# STPM01_230VAC_Rogowski.net
KiCad netlist of a schematic drawn in EAGLE
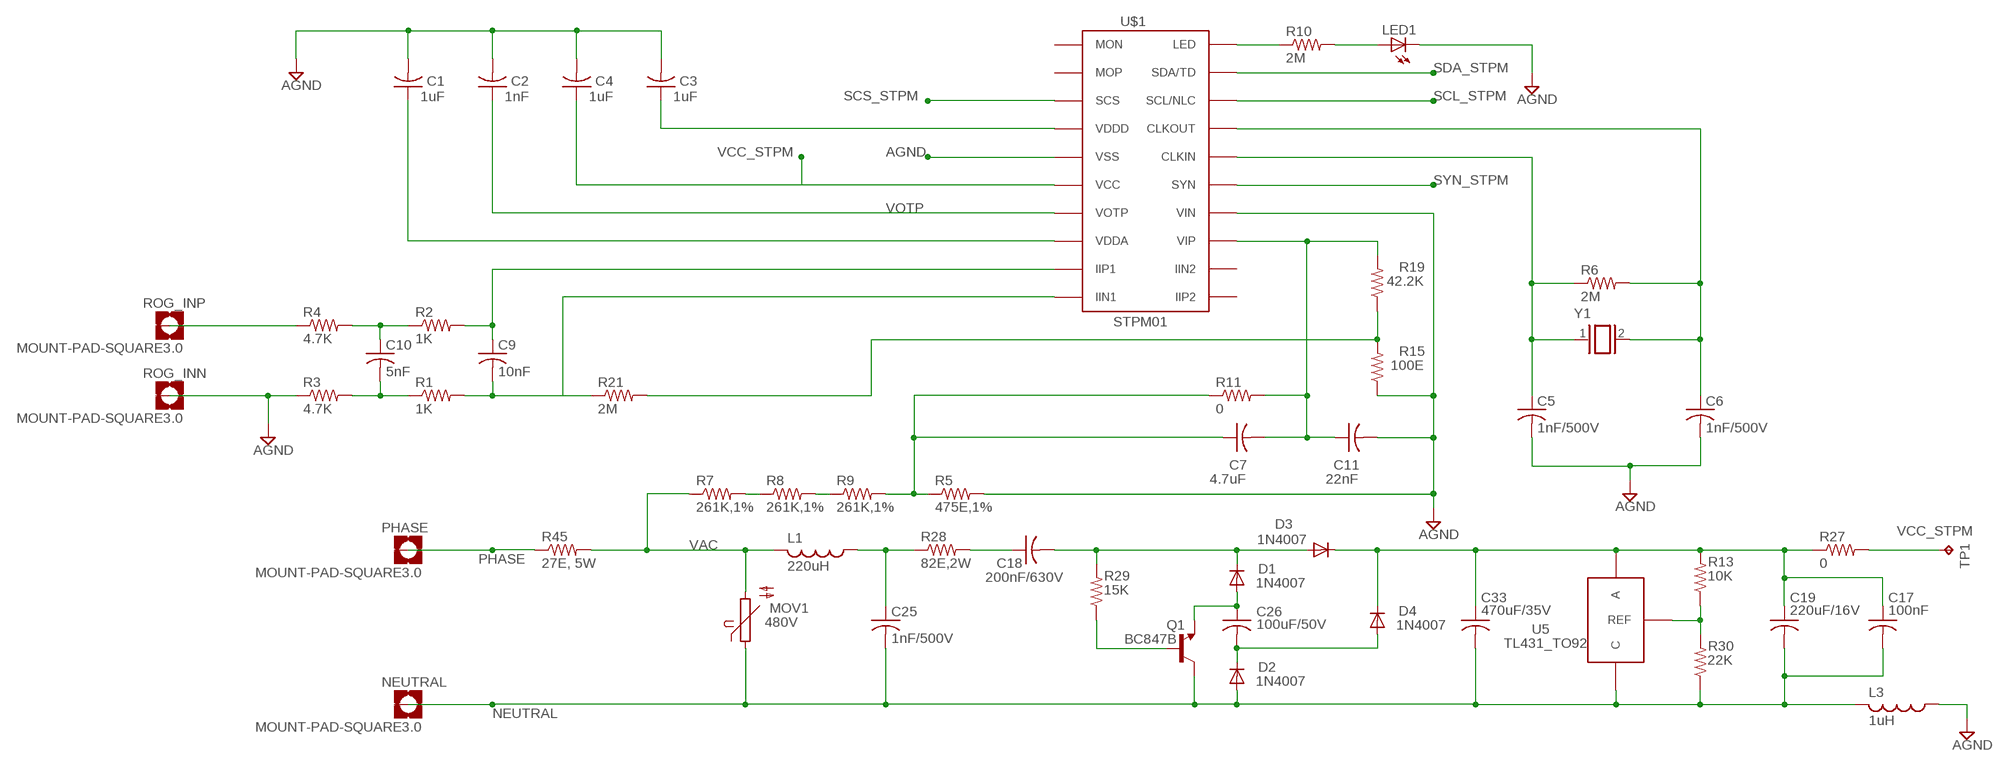
[diagram p0: schematic, sheet 1]

(export (version "E")
  (design (tool "Eeschema 10.0.6"))
  (components
    (comp (ref "C1")
      (value "1uF")
      (footprint "eagle-import:C025-060X050")
      (libsource (lib "eagle-import") (part "resistor_C-US025-060X050"))
    )
    (comp (ref "C2")
      (value "1nF")
      (footprint "eagle-import:C025-060X050")
      (libsource (lib "eagle-import") (part "resistor_C-US025-060X050"))
    )
    (comp (ref "C3")
      (value "1uF")
      (footprint "eagle-import:C025-060X050")
      (libsource (lib "eagle-import") (part "resistor_C-US025-060X050"))
    )
    (comp (ref "C4")
      (value "1uF")
      (footprint "eagle-import:C025-060X050")
      (libsource (lib "eagle-import") (part "resistor_C-US025-060X050"))
    )
    (comp (ref "C5")
      (value "1nF/500V")
      (footprint "eagle-import:C025-060X050")
      (libsource (lib "eagle-import") (part "resistor_C-US025-060X050"))
    )
    (comp (ref "C6")
      (value "1nF/500V")
      (footprint "eagle-import:C025-060X050")
      (libsource (lib "eagle-import") (part "resistor_C-US025-060X050"))
    )
    (comp (ref "C7")
      (value "4.7uF")
      (footprint "eagle-import:C050-024X044")
      (libsource (lib "eagle-import") (part "resistor_C-US050-024X044"))
    )
    (comp (ref "C9")
      (value "10nF")
      (footprint "eagle-import:C025-060X050")
      (libsource (lib "eagle-import") (part "resistor_C-US025-060X050"))
    )
    (comp (ref "C10")
      (value "5nF")
      (footprint "eagle-import:C025-060X050")
      (libsource (lib "eagle-import") (part "resistor_C-US025-060X050"))
    )
    (comp (ref "C11")
      (value "22nF")
      (footprint "eagle-import:C050-024X044")
      (libsource (lib "eagle-import") (part "resistor_C-US050-024X044"))
    )
    (comp (ref "C17")
      (value "100nF")
      (footprint "eagle-import:C025-060X050")
      (libsource (lib "eagle-import") (part "resistor_C-US025-060X050"))
    )
    (comp (ref "C18")
      (value "200nF/630V")
      (footprint "eagle-import:C050-024X044")
      (libsource (lib "eagle-import") (part "resistor_C-US050-024X044"))
    )
    (comp (ref "C19")
      (value "220uF/16V")
      (footprint "eagle-import:C025-060X050")
      (libsource (lib "eagle-import") (part "resistor_C-US025-060X050"))
    )
    (comp (ref "C25")
      (value "1nF/500V")
      (footprint "eagle-import:C025-060X050")
      (libsource (lib "eagle-import") (part "resistor_C-US025-060X050"))
    )
    (comp (ref "C26")
      (value "100uF/50V")
      (footprint "eagle-import:C050-030X075")
      (libsource (lib "eagle-import") (part "C-US050-030X075"))
    )
    (comp (ref "C33")
      (value "470uF/35V")
      (footprint "eagle-import:C025-060X050")
      (libsource (lib "eagle-import") (part "resistor_C-US025-060X050"))
    )
    (comp (ref "D1")
      (value "1N4007")
      (footprint "eagle-import:DO41-10")
      (libsource (lib "eagle-import") (part "1N4004"))
    )
    (comp (ref "D2")
      (value "1N4007")
      (footprint "eagle-import:DO41-10")
      (libsource (lib "eagle-import") (part "1N4004"))
    )
    (comp (ref "D3")
      (value "1N4007")
      (footprint "eagle-import:DO41-10")
      (libsource (lib "eagle-import") (part "1N4004"))
    )
    (comp (ref "D4")
      (value "1N4007")
      (footprint "eagle-import:DO41-10")
      (libsource (lib "eagle-import") (part "1N4004"))
    )
    (comp (ref "L1")
      (value "220uH")
      (footprint "eagle-import:0204_5")
      (libsource (lib "eagle-import") (part "L-US0204/5"))
    )
    (comp (ref "L3")
      (value "1uH")
      (footprint "eagle-import:0204_5")
      (libsource (lib "eagle-import") (part "L-US0204/5"))
    )
    (comp (ref "LED1")
      (value "LEDSMT1206")
      (footprint "eagle-import:1206")
      (libsource (lib "eagle-import") (part "LEDSMT1206"))
    )
    (comp (ref "MOV1")
      (value "480V")
      (footprint "eagle-import:S14K550")
      (libsource (lib "eagle-import") (part "S14K550"))
    )
    (comp (ref "NEUTRAL")
      (value "MOUNT-PAD-SQUARE3.0")
      (footprint "eagle-import:3,0-PAD-SQUARE")
      (libsource (lib "eagle-import") (part "MOUNT-PAD-SQUARE3.0"))
    )
    (comp (ref "PHASE")
      (value "MOUNT-PAD-SQUARE3.0")
      (footprint "eagle-import:3,0-PAD-SQUARE")
      (libsource (lib "eagle-import") (part "MOUNT-PAD-SQUARE3.0"))
    )
    (comp (ref "Q1")
      (value "BC847B")
      (footprint "eagle-import:SOT23")
      (libsource (lib "eagle-import") (part "BC847"))
    )
    (comp (ref "R1")
      (value "1K")
      (footprint "eagle-import:0922V")
      (libsource (lib "eagle-import") (part "R-US_0922V"))
    )
    (comp (ref "R2")
      (value "1K")
      (footprint "eagle-import:0922V")
      (libsource (lib "eagle-import") (part "R-US_0922V"))
    )
    (comp (ref "R3")
      (value "4.7K")
      (footprint "eagle-import:0922V")
      (libsource (lib "eagle-import") (part "R-US_0922V"))
    )
    (comp (ref "R4")
      (value "4.7K")
      (footprint "eagle-import:0922V")
      (libsource (lib "eagle-import") (part "R-US_0922V"))
    )
    (comp (ref "R5")
      (value "475E,1%")
      (footprint "eagle-import:0922V")
      (libsource (lib "eagle-import") (part "R-US_0922V"))
    )
    (comp (ref "R6")
      (value "2M")
      (footprint "eagle-import:0922V")
      (libsource (lib "eagle-import") (part "R-US_0922V"))
    )
    (comp (ref "R7")
      (value "261K,1%")
      (footprint "eagle-import:0922V")
      (libsource (lib "eagle-import") (part "R-US_0922V"))
    )
    (comp (ref "R8")
      (value "261K,1%")
      (footprint "eagle-import:0922V")
      (libsource (lib "eagle-import") (part "R-US_0922V"))
    )
    (comp (ref "R9")
      (value "261K,1%")
      (footprint "eagle-import:0922V")
      (libsource (lib "eagle-import") (part "R-US_0922V"))
    )
    (comp (ref "R10")
      (value "2M")
      (footprint "eagle-import:0922V")
      (libsource (lib "eagle-import") (part "R-US_0922V"))
    )
    (comp (ref "R11")
      (value "0")
      (footprint "eagle-import:0922V")
      (libsource (lib "eagle-import") (part "R-US_0922V"))
    )
    (comp (ref "R13")
      (value "10K")
      (footprint "eagle-import:0204_5")
      (libsource (lib "eagle-import") (part "R-US_0204/5"))
    )
    (comp (ref "R15")
      (value "100E")
      (footprint "eagle-import:0204_5")
      (libsource (lib "eagle-import") (part "R-US_0204/5"))
    )
    (comp (ref "R19")
      (value "42.2K")
      (footprint "eagle-import:0204_5")
      (libsource (lib "eagle-import") (part "R-US_0204/5"))
    )
    (comp (ref "R21")
      (value "2M")
      (footprint "eagle-import:0922V")
      (libsource (lib "eagle-import") (part "R-US_0922V"))
    )
    (comp (ref "R27")
      (value "0")
      (footprint "eagle-import:0204_5")
      (libsource (lib "eagle-import") (part "R-US_0204/5"))
    )
    (comp (ref "R28")
      (value "82E,2W")
      (footprint "eagle-import:0204_5")
      (libsource (lib "eagle-import") (part "R-US_0204/5"))
    )
    (comp (ref "R29")
      (value "15K")
      (footprint "eagle-import:0204_5")
      (libsource (lib "eagle-import") (part "R-US_0204/5"))
    )
    (comp (ref "R30")
      (value "22K")
      (footprint "eagle-import:0204_5")
      (libsource (lib "eagle-import") (part "R-US_0204/5"))
    )
    (comp (ref "R45")
      (value "27E, 5W")
      (footprint "eagle-import:0922V")
      (libsource (lib "eagle-import") (part "R-US_0922V"))
    )
    (comp (ref "ROG_INN")
      (value "MOUNT-PAD-SQUARE3.0")
      (footprint "eagle-import:3,0-PAD-SQUARE")
      (libsource (lib "eagle-import") (part "MOUNT-PAD-SQUARE3.0"))
    )
    (comp (ref "ROG_INP")
      (value "MOUNT-PAD-SQUARE3.0")
      (footprint "eagle-import:3,0-PAD-SQUARE")
      (libsource (lib "eagle-import") (part "MOUNT-PAD-SQUARE3.0"))
    )
    (comp (ref "TP1")
      (value "TPB2,54")
      (footprint "eagle-import:B2,54")
      (libsource (lib "eagle-import") (part "TPB2,54"))
    )
    (comp (ref "U$1")
      (value "STPM01")
      (footprint "eagle-import:TSSOP20")
      (libsource (lib "eagle-import") (part "STPM01"))
    )
    (comp (ref "U5")
      (value "TL431_TO92")
      (footprint "eagle-import:TO92-")
      (libsource (lib "eagle-import") (part "TL431AIZ"))
    )
    (comp (ref "Y1")
      (value "XTAL/S")
      (footprint "eagle-import:QS")
      (libsource (lib "eagle-import") (part "XTAL/S"))
    )
  )
  (nets
    (net (code "1") (name "/NEUTRAL") (class "Default")
      (node (ref "C17") (pin "2") (pinfunction "2_2") (pintype "passive"))
      (node (ref "C19") (pin "2") (pinfunction "2_2") (pintype "passive"))
      (node (ref "C25") (pin "2") (pinfunction "2_2") (pintype "passive"))
      (node (ref "C33") (pin "2") (pinfunction "2_2") (pintype "passive"))
      (node (ref "D2") (pin "A") (pinfunction "A_A") (pintype "passive"))
      (node (ref "L3") (pin "2") (pinfunction "2_2") (pintype "passive"))
      (node (ref "MOV1") (pin "1") (pinfunction "1_1") (pintype "passive"))
      (node (ref "Q1") (pin "3") (pinfunction "C_3") (pintype "passive"))
      (node (ref "R30") (pin "1") (pinfunction "1_1") (pintype "passive"))
      (node (ref "U5") (pin "1") (pinfunction "C_1") (pintype "bidirectional"))
    )
    (net (code "2") (name "/PHASE") (class "Default")
      (node (ref "R45") (pin "1") (pinfunction "1_1") (pintype "passive"))
    )
    (net (code "3") (name "/SCL_STPM") (class "Default")
      (node (ref "U$1") (pin "P$18") (pinfunction "SCL/NLC_P$18") (pintype "bidirectional"))
    )
    (net (code "4") (name "/SCS_STPM") (class "Default")
      (node (ref "U$1") (pin "P$3") (pinfunction "SCS_P$3") (pintype "bidirectional"))
    )
    (net (code "5") (name "/SDA_STPM") (class "Default")
      (node (ref "U$1") (pin "P$19") (pinfunction "SDA/TD_P$19") (pintype "bidirectional"))
    )
    (net (code "6") (name "/SYN_STPM") (class "Default")
      (node (ref "U$1") (pin "P$15") (pinfunction "SYN_P$15") (pintype "bidirectional"))
    )
    (net (code "7") (name "/VAC") (class "Default")
      (node (ref "L1") (pin "2") (pinfunction "2_2") (pintype "passive"))
      (node (ref "MOV1") (pin "2") (pinfunction "2_2") (pintype "passive"))
      (node (ref "R45") (pin "2") (pinfunction "2_2") (pintype "passive"))
      (node (ref "R7") (pin "1") (pinfunction "1_1") (pintype "passive"))
    )
    (net (code "8") (name "/VCC_STPM") (class "Default")
      (node (ref "C4") (pin "1") (pinfunction "1_1") (pintype "passive"))
      (node (ref "R27") (pin "2") (pinfunction "2_2") (pintype "passive"))
      (node (ref "TP1") (pin "TP") (pinfunction "TP_TP") (pintype "input"))
      (node (ref "U$1") (pin "P$6") (pinfunction "VCC_P$6") (pintype "power_in"))
    )
    (net (code "9") (name "/VOTP") (class "Default")
      (node (ref "C2") (pin "1") (pinfunction "1_1") (pintype "passive"))
      (node (ref "U$1") (pin "P$7") (pinfunction "VOTP_P$7") (pintype "power_in"))
    )
    (net (code "10") (name "AGND") (class "Default")
      (node (ref "C1") (pin "2") (pinfunction "2_2") (pintype "passive"))
      (node (ref "C11") (pin "2") (pinfunction "2_2") (pintype "passive"))
      (node (ref "C2") (pin "2") (pinfunction "2_2") (pintype "passive"))
      (node (ref "C3") (pin "2") (pinfunction "2_2") (pintype "passive"))
      (node (ref "C4") (pin "2") (pinfunction "2_2") (pintype "passive"))
      (node (ref "C5") (pin "2") (pinfunction "2_2") (pintype "passive"))
      (node (ref "C6") (pin "2") (pinfunction "2_2") (pintype "passive"))
      (node (ref "L3") (pin "1") (pinfunction "1_1") (pintype "passive"))
      (node (ref "LED1") (pin "C") (pinfunction "C_C") (pintype "passive"))
      (node (ref "R15") (pin "1") (pinfunction "1_1") (pintype "passive"))
      (node (ref "R3") (pin "1") (pinfunction "1_1") (pintype "passive"))
      (node (ref "R5") (pin "2") (pinfunction "2_2") (pintype "passive"))
      (node (ref "U$1") (pin "P$14") (pinfunction "VIN_P$14") (pintype "input"))
      (node (ref "U$1") (pin "P$5") (pinfunction "VSS_P$5") (pintype "power_in"))
    )
    (net (code "11") (name "Net-(C7-Pad1)") (class "Default")
      (node (ref "C7") (pin "1") (pinfunction "1_1") (pintype "passive"))
      (node (ref "R11") (pin "1") (pinfunction "1_1") (pintype "passive"))
      (node (ref "R5") (pin "1") (pinfunction "1_1") (pintype "passive"))
      (node (ref "R9") (pin "2") (pinfunction "2_2") (pintype "passive"))
    )
    (net (code "12") (name "Net-(C10-Pad1)") (class "Default")
      (node (ref "C10") (pin "1") (pinfunction "1_1") (pintype "passive"))
      (node (ref "R2") (pin "1") (pinfunction "1_1") (pintype "passive"))
      (node (ref "R4") (pin "2") (pinfunction "2_2") (pintype "passive"))
    )
    (net (code "13") (name "Net-(C10-Pad2)") (class "Default")
      (node (ref "C10") (pin "2") (pinfunction "2_2") (pintype "passive"))
      (node (ref "R1") (pin "1") (pinfunction "1_1") (pintype "passive"))
      (node (ref "R3") (pin "2") (pinfunction "2_2") (pintype "passive"))
    )
    (net (code "14") (name "Net-(C18-Pad1)") (class "Default")
      (node (ref "C18") (pin "1") (pinfunction "1_1") (pintype "passive"))
      (node (ref "R28") (pin "2") (pinfunction "2_2") (pintype "passive"))
    )
    (net (code "15") (name "Net-(C18-Pad2)") (class "Default")
      (node (ref "C18") (pin "2") (pinfunction "2_2") (pintype "passive"))
      (node (ref "D1") (pin "C") (pinfunction "C_C") (pintype "passive"))
      (node (ref "D3") (pin "A") (pinfunction "A_A") (pintype "passive"))
      (node (ref "R29") (pin "2") (pinfunction "2_2") (pintype "passive"))
    )
    (net (code "16") (name "Net-(C25-Pad1)") (class "Default")
      (node (ref "C25") (pin "1") (pinfunction "1_1") (pintype "passive"))
      (node (ref "L1") (pin "1") (pinfunction "1_1") (pintype "passive"))
      (node (ref "R28") (pin "1") (pinfunction "1_1") (pintype "passive"))
    )
    (net (code "17") (name "Net-(C26-Pad2)") (class "Default")
      (node (ref "C26") (pin "2") (pinfunction "2_2") (pintype "passive"))
      (node (ref "D2") (pin "C") (pinfunction "C_C") (pintype "passive"))
      (node (ref "D4") (pin "A") (pinfunction "A_A") (pintype "passive"))
    )
    (net (code "18") (name "Net-(LED1-PadA)") (class "Default")
      (node (ref "LED1") (pin "A") (pinfunction "A_A") (pintype "passive"))
      (node (ref "R10") (pin "2") (pinfunction "2_2") (pintype "passive"))
    )
    (net (code "19") (name "Net-(Q1-B)") (class "Default")
      (node (ref "Q1") (pin "1") (pinfunction "B_1") (pintype "passive"))
      (node (ref "R29") (pin "1") (pinfunction "1_1") (pintype "passive"))
    )
    (net (code "20") (name "Net-(Q1-E)") (class "Default")
      (node (ref "C26") (pin "1") (pinfunction "1_1") (pintype "passive"))
      (node (ref "D1") (pin "A") (pinfunction "A_A") (pintype "passive"))
      (node (ref "Q1") (pin "2") (pinfunction "E_2") (pintype "passive"))
    )
    (net (code "21") (name "Net-(R7-Pad2)") (class "Default")
      (node (ref "R7") (pin "2") (pinfunction "2_2") (pintype "passive"))
      (node (ref "R8") (pin "1") (pinfunction "1_1") (pintype "passive"))
    )
    (net (code "22") (name "Net-(R8-Pad2)") (class "Default")
      (node (ref "R8") (pin "2") (pinfunction "2_2") (pintype "passive"))
      (node (ref "R9") (pin "1") (pinfunction "1_1") (pintype "passive"))
    )
    (net (code "23") (name "Net-(R15-Pad2)") (class "Default")
      (node (ref "R15") (pin "2") (pinfunction "2_2") (pintype "passive"))
      (node (ref "R19") (pin "1") (pinfunction "1_1") (pintype "passive"))
      (node (ref "R21") (pin "2") (pinfunction "2_2") (pintype "passive"))
    )
    (net (code "24") (name "Net-(U$1-CLKIN)") (class "Default")
      (node (ref "C5") (pin "1") (pinfunction "1_1") (pintype "passive"))
      (node (ref "R6") (pin "1") (pinfunction "1_1") (pintype "passive"))
      (node (ref "U$1") (pin "P$16") (pinfunction "CLKIN_P$16") (pintype "bidirectional"))
      (node (ref "Y1") (pin "1") (pinfunction "1_1") (pintype "passive"))
    )
    (net (code "25") (name "Net-(U$1-CLKOUT)") (class "Default")
      (node (ref "C6") (pin "1") (pinfunction "1_1") (pintype "passive"))
      (node (ref "R6") (pin "2") (pinfunction "2_2") (pintype "passive"))
      (node (ref "U$1") (pin "P$17") (pinfunction "CLKOUT_P$17") (pintype "bidirectional"))
      (node (ref "Y1") (pin "2") (pinfunction "2_2") (pintype "passive"))
    )
    (net (code "26") (name "Net-(U$1-IIN1)") (class "Default")
      (node (ref "C9") (pin "2") (pinfunction "2_2") (pintype "passive"))
      (node (ref "R1") (pin "2") (pinfunction "2_2") (pintype "passive"))
      (node (ref "R21") (pin "1") (pinfunction "1_1") (pintype "passive"))
      (node (ref "U$1") (pin "P$10") (pinfunction "IIN1_P$10") (pintype "input"))
    )
    (net (code "27") (name "Net-(U$1-IIP1)") (class "Default")
      (node (ref "C9") (pin "1") (pinfunction "1_1") (pintype "passive"))
      (node (ref "R2") (pin "2") (pinfunction "2_2") (pintype "passive"))
      (node (ref "U$1") (pin "P$9") (pinfunction "IIP1_P$9") (pintype "input"))
    )
    (net (code "28") (name "Net-(U$1-LED)") (class "Default")
      (node (ref "R10") (pin "1") (pinfunction "1_1") (pintype "passive"))
      (node (ref "U$1") (pin "P$20") (pinfunction "LED_P$20") (pintype "output"))
    )
    (net (code "29") (name "Net-(U$1-VDDA)") (class "Default")
      (node (ref "C1") (pin "1") (pinfunction "1_1") (pintype "passive"))
      (node (ref "U$1") (pin "P$8") (pinfunction "VDDA_P$8") (pintype "output"))
    )
    (net (code "30") (name "Net-(U$1-VDDD)") (class "Default")
      (node (ref "C3") (pin "1") (pinfunction "1_1") (pintype "passive"))
      (node (ref "U$1") (pin "P$4") (pinfunction "VDDD_P$4") (pintype "output"))
    )
    (net (code "31") (name "Net-(U$1-VIP)") (class "Default")
      (node (ref "C11") (pin "1") (pinfunction "1_1") (pintype "passive"))
      (node (ref "C7") (pin "2") (pinfunction "2_2") (pintype "passive"))
      (node (ref "R11") (pin "2") (pinfunction "2_2") (pintype "passive"))
      (node (ref "R19") (pin "2") (pinfunction "2_2") (pintype "passive"))
      (node (ref "U$1") (pin "P$13") (pinfunction "VIP_P$13") (pintype "input"))
    )
    (net (code "32") (name "Net-(U5-A)") (class "Default")
      (node (ref "C17") (pin "1") (pinfunction "1_1") (pintype "passive"))
      (node (ref "C19") (pin "1") (pinfunction "1_1") (pintype "passive"))
      (node (ref "C33") (pin "1") (pinfunction "1_1") (pintype "passive"))
      (node (ref "D3") (pin "C") (pinfunction "C_C") (pintype "passive"))
      (node (ref "D4") (pin "C") (pinfunction "C_C") (pintype "passive"))
      (node (ref "R13") (pin "2") (pinfunction "2_2") (pintype "passive"))
      (node (ref "R27") (pin "1") (pinfunction "1_1") (pintype "passive"))
      (node (ref "U5") (pin "2") (pinfunction "A_2") (pintype "bidirectional"))
    )
    (net (code "33") (name "Net-(U5-REF)") (class "Default")
      (node (ref "R13") (pin "1") (pinfunction "1_1") (pintype "passive"))
      (node (ref "R30") (pin "2") (pinfunction "2_2") (pintype "passive"))
      (node (ref "U5") (pin "3") (pinfunction "REF_3") (pintype "input"))
    )
    (net (code "34") (name "unconnected-(NEUTRAL-MOUNT-PadB3,0)") (class "Default")
      (node (ref "NEUTRAL") (pin "B3,0") (pinfunction "MOUNT_B3,0") (pintype "passive"))
    )
    (net (code "35") (name "unconnected-(PHASE-MOUNT-PadB3,0)") (class "Default")
      (node (ref "PHASE") (pin "B3,0") (pinfunction "MOUNT_B3,0") (pintype "passive"))
    )
    (net (code "36") (name "unconnected-(R4-Pad1)") (class "Default")
      (node (ref "R4") (pin "1") (pinfunction "1_1") (pintype "passive"))
    )
    (net (code "37") (name "unconnected-(ROG_INN-MOUNT-PadB3,0)") (class "Default")
      (node (ref "ROG_INN") (pin "B3,0") (pinfunction "MOUNT_B3,0") (pintype "passive"))
    )
    (net (code "38") (name "unconnected-(ROG_INP-MOUNT-PadB3,0)") (class "Default")
      (node (ref "ROG_INP") (pin "B3,0") (pinfunction "MOUNT_B3,0") (pintype "passive"))
    )
    (net (code "39") (name "unconnected-(U$1-IIN2-PadP$12)") (class "Default")
      (node (ref "U$1") (pin "P$12") (pinfunction "IIN2_P$12") (pintype "input"))
    )
    (net (code "40") (name "unconnected-(U$1-IIP2-PadP$11)") (class "Default")
      (node (ref "U$1") (pin "P$11") (pinfunction "IIP2_P$11") (pintype "input"))
    )
    (net (code "41") (name "unconnected-(U$1-MON-PadP$1)") (class "Default")
      (node (ref "U$1") (pin "P$1") (pinfunction "MON_P$1") (pintype "output"))
    )
    (net (code "42") (name "unconnected-(U$1-MOP-PadP$2)") (class "Default")
      (node (ref "U$1") (pin "P$2") (pinfunction "MOP_P$2") (pintype "output"))
    )
  )
)
